# hv_power.net
KiCad netlist of a schematic drawn in EAGLE
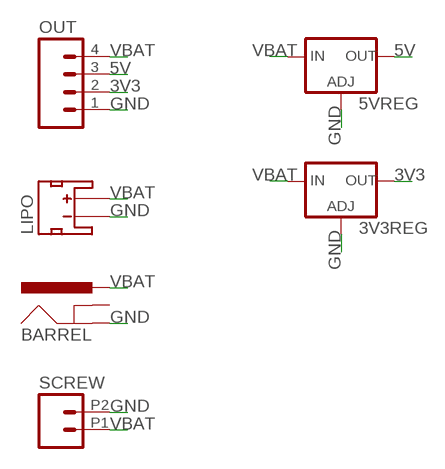
[diagram p0: schematic, sheet 1]

(export (version "E")
  (design (tool "Eeschema 10.0.6"))
  (components
    (comp (ref "3V3REG")
      (value "V_REG_317DPACK")
      (footprint "eagle-import:V-REG_DPACK")
      (libsource (lib "eagle-import") (part "V_REG_317DPACK"))
    )
    (comp (ref "5VREG")
      (value "V_REG_317DPACK")
      (footprint "eagle-import:V-REG_DPACK")
      (libsource (lib "eagle-import") (part "V_REG_317DPACK"))
    )
    (comp (ref "BARREL")
      (value "POWER_JACKPTH_BREAD")
      (footprint "eagle-import:POWER_JACK_PTH_BREAD")
      (libsource (lib "eagle-import") (part "POWER_JACKPTH_BREAD"))
    )
    (comp (ref "LIPO")
      (value "JST_2MM_MALE")
      (footprint "eagle-import:JST-2-SMD")
      (libsource (lib "eagle-import") (part "JST_2MM_MALE"))
    )
    (comp (ref "OUT")
      (value "M04PTH")
      (footprint "eagle-import:1X04")
      (libsource (lib "eagle-import") (part "M04PTH"))
    )
    (comp (ref "SCREW")
      (value "M022.54MM_SCREWTERM")
      (footprint "eagle-import:1X02_2.54_SCREWTERM")
      (libsource (lib "eagle-import") (part "M022.54MM_SCREWTERM"))
    )
  )
  (nets
    (net (code "1") (name "/3V3") (class "Default")
      (node (ref "3V3REG") (pin "4") (pinfunction "OUT_4") (pintype "output"))
      (node (ref "OUT") (pin "2") (pinfunction "2_2") (pintype "passive"))
    )
    (net (code "2") (name "/5V") (class "Default")
      (node (ref "5VREG") (pin "4") (pinfunction "OUT_4") (pintype "output"))
      (node (ref "OUT") (pin "3") (pinfunction "3_3") (pintype "passive"))
    )
    (net (code "3") (name "/GND") (class "Default")
      (node (ref "3V3REG") (pin "1") (pinfunction "ADJ_1") (pintype "input"))
      (node (ref "5VREG") (pin "1") (pinfunction "ADJ_1") (pintype "input"))
      (node (ref "BARREL") (pin "GND") (pinfunction "GND_GND") (pintype "bidirectional"))
      (node (ref "LIPO") (pin "1") (pinfunction "-_1") (pintype "bidirectional"))
      (node (ref "OUT") (pin "1") (pinfunction "1_1") (pintype "passive"))
      (node (ref "SCREW") (pin "P2") (pinfunction "2_P2") (pintype "passive"))
    )
    (net (code "4") (name "/VBAT") (class "Default")
      (node (ref "3V3REG") (pin "3") (pinfunction "IN_3") (pintype "input"))
      (node (ref "5VREG") (pin "3") (pinfunction "IN_3") (pintype "input"))
      (node (ref "BARREL") (pin "PWR") (pinfunction "PWR_PWR") (pintype "bidirectional"))
      (node (ref "LIPO") (pin "2") (pinfunction "+_2") (pintype "bidirectional"))
      (node (ref "OUT") (pin "4") (pinfunction "4_4") (pintype "passive"))
      (node (ref "SCREW") (pin "P1") (pinfunction "1_P1") (pintype "passive"))
    )
    (net (code "5") (name "unconnected-(BARREL-PadGNDBREAK)") (class "Default")
      (node (ref "BARREL") (pin "GNDBREAK") (pinfunction "GNDBREAK_GNDBREAK") (pintype "bidirectional"))
    )
    (net (code "6") (name "unconnected-(LIPO-PAD1-PadNC1)") (class "Default")
      (node (ref "LIPO") (pin "NC1") (pinfunction "PAD1_NC1") (pintype "bidirectional"))
    )
    (net (code "7") (name "unconnected-(LIPO-PAD2-PadNC2)") (class "Default")
      (node (ref "LIPO") (pin "NC2") (pinfunction "PAD2_NC2") (pintype "bidirectional"))
    )
  )
)
